# Mini_Comm_sch.net
KiCad netlist of a schematic drawn in Altium Designer
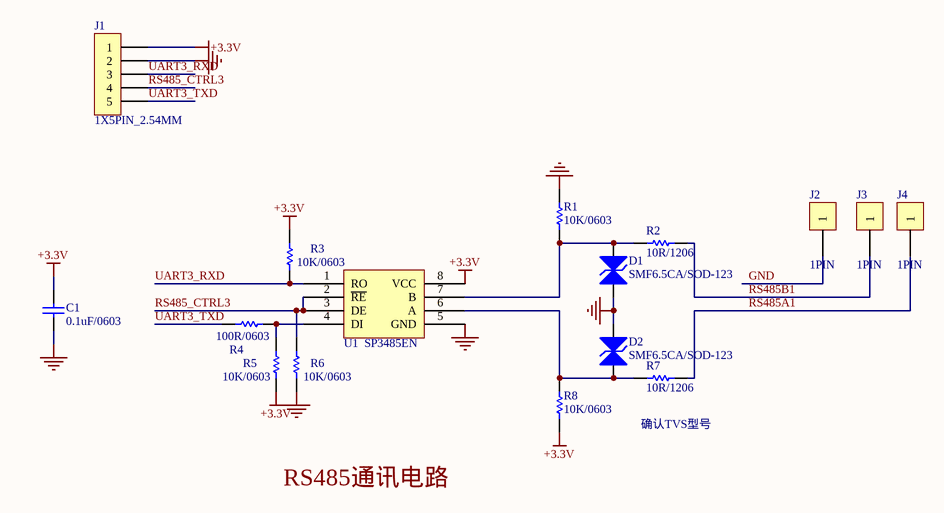
[diagram p0: Mini_Comm_sch.SchDoc]

(export (version "E")
  (design (tool "Eeschema 10.0.6"))
  (components
    (comp (ref "C1")
      (value "0.1uF/0603")
      (footprint "CAP/SMT/0603C")
      (libsource (lib "Menred_原理图 封装库") (part "CAP/CAP/SMT/0603C"))
    )
    (comp (ref "D1")
      (value "SMF6.5CA/SOD-123")
      (footprint "D/SMT/SOD123")
      (libsource (lib "Menred_原理图 封装库") (part "D/TVS/SMT/SMF13CA/SOD-123"))
    )
    (comp (ref "D2")
      (value "SMF6.5CA/SOD-123")
      (footprint "D/SMT/SOD123")
      (libsource (lib "Menred_原理图 封装库") (part "D/TVS/SMT/SMF13CA/SOD-123"))
    )
    (comp (ref "J1")
      (value "1X5PIN_2.54MM")
      (footprint "CON/DIP/1×5PIN/2.0MM")
      (description "Connector")
      (libsource (lib "Menred_原理图 封装库") (part "CON/DIP/1X5PIN_2.54MM"))
    )
    (comp (ref "J2")
      (value "1PIN")
      (footprint "CON/DIP/1PIN")
      (description "Connector")
      (libsource (lib "Menred_原理图 封装库") (part "CON/DIP/1PIN"))
    )
    (comp (ref "J3")
      (value "1PIN")
      (footprint "CON/DIP/1PIN")
      (description "Connector")
      (libsource (lib "Menred_原理图 封装库") (part "CON/DIP/1PIN"))
    )
    (comp (ref "J4")
      (value "1PIN")
      (footprint "CON/DIP/1PIN")
      (description "Connector")
      (libsource (lib "Menred_原理图 封装库") (part "CON/DIP/1PIN"))
    )
    (comp (ref "R1")
      (value "10K/0603")
      (footprint "0603R")
      (libsource (lib "Menred_原理图 封装库") (part "RES/RES/SMT/0603"))
    )
    (comp (ref "R2")
      (value "10R/1206")
      (footprint "1206R")
      (libsource (lib "Menred_原理图 封装库") (part "RES/RES/SMT/1206"))
    )
    (comp (ref "R3")
      (value "10K/0603")
      (footprint "0603R")
      (libsource (lib "Menred_原理图 封装库") (part "RES/RES/SMT/0603"))
    )
    (comp (ref "R4")
      (value "100R/0603")
      (footprint "0603R")
      (libsource (lib "Menred_原理图 封装库") (part "RES/RES/SMT/0603"))
    )
    (comp (ref "R5")
      (value "10K/0603")
      (footprint "0603R")
      (libsource (lib "Menred_原理图 封装库") (part "RES/RES/SMT/0603"))
    )
    (comp (ref "R6")
      (value "10K/0603")
      (footprint "0603R")
      (libsource (lib "Menred_原理图 封装库") (part "RES/RES/SMT/0603"))
    )
    (comp (ref "R7")
      (value "10R/1206")
      (footprint "1206R")
      (libsource (lib "Menred_原理图 封装库") (part "RES/RES/SMT/1206"))
    )
    (comp (ref "R8")
      (value "10K/0603")
      (footprint "0603R")
      (libsource (lib "Menred_原理图 封装库") (part "RES/RES/SMT/0603"))
    )
    (comp (ref "U1") (value "SP3485EN") (footprint "SOIC-8") (libsource (lib "*") (part "SP485EN")))
  )
  (nets
    (net (code "1") (name "+3.3V") (class "Default")
      (node (ref "C1") (pin "2") (pinfunction "2_2") (pintype "passive"))
      (node (ref "J1") (pin "1") (pinfunction "1_1") (pintype "passive"))
      (node (ref "R3") (pin "2") (pinfunction "2_2") (pintype "passive"))
      (node (ref "R5") (pin "1") (pinfunction "1_1") (pintype "passive"))
      (node (ref "R8") (pin "2") (pinfunction "2_2") (pintype "passive"))
      (node (ref "U1") (pin "8") (pinfunction "VCC_8") (pintype "passive"))
    )
    (net (code "2") (name "/RS485A1") (class "Default")
      (node (ref "J4") (pin "1") (pinfunction "1_1") (pintype "passive"))
      (node (ref "R7") (pin "2") (pinfunction "2_2") (pintype "passive"))
    )
    (net (code "3") (name "/RS485B1") (class "Default")
      (node (ref "J3") (pin "1") (pinfunction "1_1") (pintype "passive"))
      (node (ref "R2") (pin "2") (pinfunction "2_2") (pintype "passive"))
    )
    (net (code "4") (name "/RS485_CTRL3") (class "Default")
      (node (ref "J1") (pin "4") (pinfunction "4_4") (pintype "passive"))
      (node (ref "R6") (pin "1") (pinfunction "1_1") (pintype "passive"))
      (node (ref "U1") (pin "2") (pinfunction "~{RE}_2") (pintype "passive"))
      (node (ref "U1") (pin "3") (pinfunction "DE_3") (pintype "passive"))
    )
    (net (code "6") (name "/UART3_RXD") (class "Default")
      (node (ref "J1") (pin "3") (pinfunction "3_3") (pintype "passive"))
      (node (ref "R3") (pin "1") (pinfunction "1_1") (pintype "passive"))
      (node (ref "U1") (pin "1") (pinfunction "RO_1") (pintype "passive"))
    )
    (net (code "7") (name "/UART3_TXD") (class "Default")
      (node (ref "J1") (pin "5") (pinfunction "5_5") (pintype "passive"))
      (node (ref "R4") (pin "2") (pinfunction "2_2") (pintype "passive"))
    )
    (net (code "8") (name "GND") (class "Default")
      (node (ref "C1") (pin "1") (pinfunction "1_1") (pintype "passive"))
      (node (ref "D1") (pin "2") (pinfunction "K_2") (pintype "passive"))
      (node (ref "D2") (pin "2") (pinfunction "K_2") (pintype "passive"))
      (node (ref "J1") (pin "2") (pinfunction "2_2") (pintype "passive"))
      (node (ref "J2") (pin "1") (pinfunction "1_1") (pintype "passive"))
      (node (ref "R1") (pin "1") (pinfunction "1_1") (pintype "passive"))
      (node (ref "R6") (pin "2") (pinfunction "2_2") (pintype "passive"))
      (node (ref "U1") (pin "5") (pinfunction "GND_5") (pintype "passive"))
    )
    (net (code "9") (name "Net-(D1-A)") (class "Default")
      (node (ref "D1") (pin "1") (pinfunction "A_1") (pintype "passive"))
      (node (ref "R1") (pin "2") (pinfunction "2_2") (pintype "passive"))
      (node (ref "R2") (pin "1") (pinfunction "1_1") (pintype "passive"))
      (node (ref "U1") (pin "7") (pinfunction "B_7") (pintype "passive"))
    )
    (net (code "10") (name "Net-(D2-A)") (class "Default")
      (node (ref "D2") (pin "1") (pinfunction "A_1") (pintype "passive"))
      (node (ref "R7") (pin "1") (pinfunction "1_1") (pintype "passive"))
      (node (ref "R8") (pin "1") (pinfunction "1_1") (pintype "passive"))
      (node (ref "U1") (pin "6") (pinfunction "A_6") (pintype "passive"))
    )
    (net (code "11") (name "Net-(U1-DI)") (class "Default")
      (node (ref "R4") (pin "1") (pinfunction "1_1") (pintype "passive"))
      (node (ref "R5") (pin "2") (pinfunction "2_2") (pintype "passive"))
      (node (ref "U1") (pin "4") (pinfunction "DI_4") (pintype "passive"))
    )
  )
)
